# AVRispMK2_V2.net
KiCad netlist of a schematic drawn in EAGLE
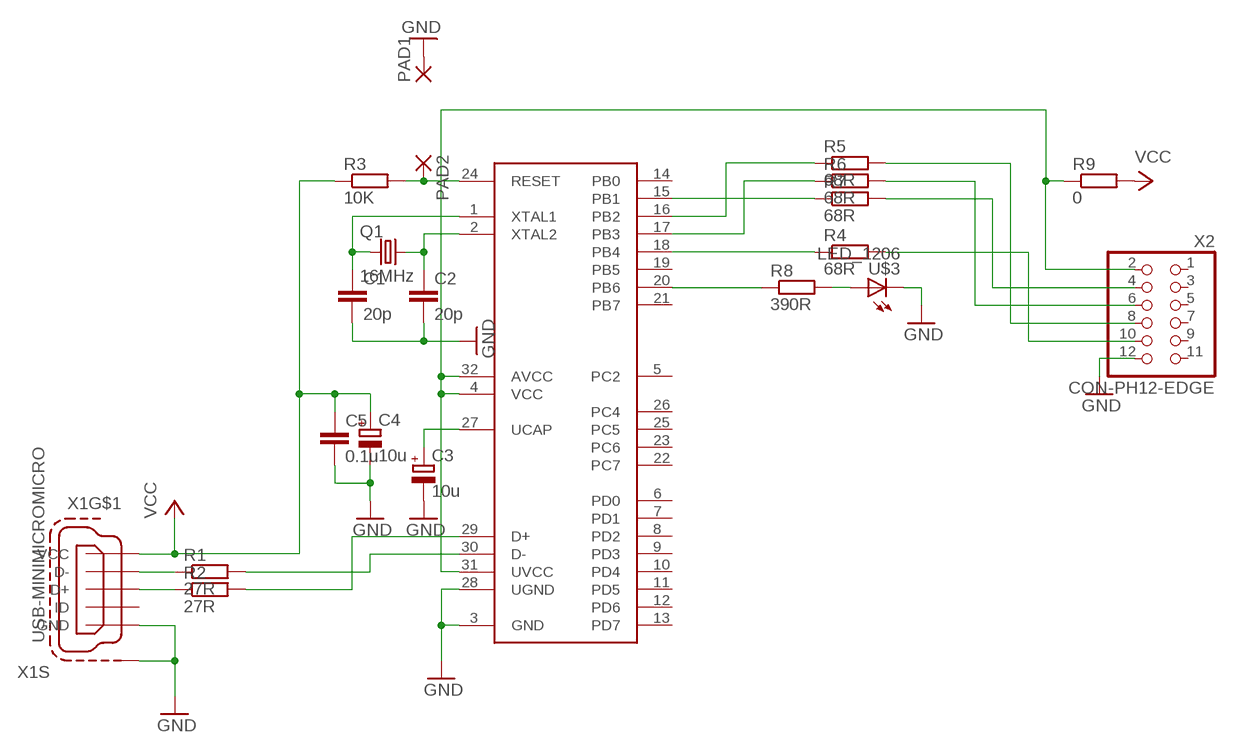
[diagram p0: schematic, sheet 1]

(export (version "E")
  (design (tool "Eeschema 10.0.6"))
  (components
    (comp (ref "C1")
      (value "20p")
      (footprint "eagle-import:C1206")
      (libsource (lib "eagle-import") (part "C-EUC1206"))
    )
    (comp (ref "C2")
      (value "20p")
      (footprint "eagle-import:C1206")
      (libsource (lib "eagle-import") (part "C-EUC1206"))
    )
    (comp (ref "C3")
      (value "10u")
      (footprint "eagle-import:SMC_A")
      (libsource (lib "eagle-import") (part "CPOL-EUSMCA"))
    )
    (comp (ref "C4")
      (value "10u")
      (footprint "eagle-import:SMC_A")
      (libsource (lib "eagle-import") (part "CPOL-EUSMCA"))
    )
    (comp (ref "C5")
      (value "0.1u")
      (footprint "eagle-import:C1206")
      (libsource (lib "eagle-import") (part "C-EUC1206"))
    )
    (comp (ref "PAD1")
      (value "SMD2")
      (footprint "eagle-import:SMD1,27-2,54")
      (libsource (lib "eagle-import") (part "SMD2"))
    )
    (comp (ref "PAD2")
      (value "SMD2")
      (footprint "eagle-import:SMD1,27-2,54")
      (libsource (lib "eagle-import") (part "SMD2"))
    )
    (comp (ref "Q1")
      (value "16MHz")
      (footprint "eagle-import:CRYSTAL-3225")
      (libsource (lib "eagle-import") (part "CRYSTAL3225"))
    )
    (comp (ref "R1")
      (value "27R")
      (footprint "eagle-import:R1206")
      (libsource (lib "eagle-import") (part "R-EU_R1206"))
    )
    (comp (ref "R2")
      (value "27R")
      (footprint "eagle-import:R1206")
      (libsource (lib "eagle-import") (part "R-EU_R1206"))
    )
    (comp (ref "R3")
      (value "10K")
      (footprint "eagle-import:R1206")
      (libsource (lib "eagle-import") (part "R-EU_R1206"))
    )
    (comp (ref "R4")
      (value "68R")
      (footprint "eagle-import:R1206")
      (libsource (lib "eagle-import") (part "R-EU_R1206"))
    )
    (comp (ref "R5")
      (value "68R")
      (footprint "eagle-import:R1206")
      (libsource (lib "eagle-import") (part "R-EU_R1206"))
    )
    (comp (ref "R6")
      (value "68R")
      (footprint "eagle-import:R1206")
      (libsource (lib "eagle-import") (part "R-EU_R1206"))
    )
    (comp (ref "R7")
      (value "68R")
      (footprint "eagle-import:R1206")
      (libsource (lib "eagle-import") (part "R-EU_R1206"))
    )
    (comp (ref "R8")
      (value "390R")
      (footprint "eagle-import:R1206")
      (libsource (lib "eagle-import") (part "R-EU_R1206"))
    )
    (comp (ref "R9")
      (value "0")
      (footprint "eagle-import:R1206")
      (libsource (lib "eagle-import") (part "R-EU_R1206"))
    )
    (comp (ref "U$1")
      (value "AT90USB162")
      (footprint "eagle-import:VQFP32")
      (libsource (lib "eagle-import") (part "AT90USB162"))
    )
    (comp (ref "U$3")
      (value "LED_1206")
      (footprint "eagle-import:LED1206")
      (libsource (lib "eagle-import") (part "LED_1206"))
    )
    (comp (ref "X1")
      (value "USB-MINIMICROMICRO")
      (footprint "eagle-import:USB-B-MICRO-SMD")
      (libsource (lib "eagle-import") (part "USB-MINIMICROMICRO"))
    )
    (comp (ref "X2")
      (value "CON-PH12-EDGE")
      (footprint "eagle-import:ML12_EDGE_SMD")
      (libsource (lib "eagle-import") (part "CON-PH12-EDGE"))
    )
  )
  (nets
    (net (code "1") (name "GND") (class "Default")
      (node (ref "C1") (pin "2") (pinfunction "2_2") (pintype "passive"))
      (node (ref "C2") (pin "2") (pinfunction "2_2") (pintype "passive"))
      (node (ref "C3") (pin "-") (pinfunction "-_-") (pintype "passive"))
      (node (ref "C4") (pin "-") (pinfunction "-_-") (pintype "passive"))
      (node (ref "C5") (pin "2") (pinfunction "2_2") (pintype "passive"))
      (node (ref "PAD1") (pin "1") (pinfunction "P_1") (pintype "passive"))
      (node (ref "U$1") (pin "28") (pinfunction "UGND_28") (pintype "bidirectional"))
      (node (ref "U$1") (pin "3") (pinfunction "GND_3") (pintype "power_in"))
      (node (ref "U$3") (pin "C") (pinfunction "C_C") (pintype "passive"))
      (node (ref "X1") (pin "GND") (pinfunction "GND_GND") (pintype "passive"))
      (node (ref "X1") (pin "SHIELD1") (pinfunction "S1_SHIELD1") (pintype "passive"))
      (node (ref "X1") (pin "SHIELD2") (pinfunction "S1_SHIELD2") (pintype "passive"))
      (node (ref "X1") (pin "SHIELD3") (pinfunction "S1_SHIELD3") (pintype "passive"))
      (node (ref "X2") (pin "12") (pinfunction "12_12") (pintype "passive"))
    )
    (net (code "2") (name "Net-(PAD2-P)") (class "Default")
      (node (ref "PAD2") (pin "1") (pinfunction "P_1") (pintype "passive"))
      (node (ref "R3") (pin "2") (pinfunction "2_2") (pintype "passive"))
      (node (ref "U$1") (pin "24") (pinfunction "RESET_24") (pintype "bidirectional"))
    )
    (net (code "3") (name "Net-(Q1-1)") (class "Default")
      (node (ref "C1") (pin "1") (pinfunction "1_1") (pintype "passive"))
      (node (ref "Q1") (pin "P$2") (pinfunction "1_P$2") (pintype "passive"))
      (node (ref "U$1") (pin "1") (pinfunction "XTAL1_1") (pintype "bidirectional"))
    )
    (net (code "4") (name "Net-(Q1-2)") (class "Default")
      (node (ref "C2") (pin "1") (pinfunction "1_1") (pintype "passive"))
      (node (ref "Q1") (pin "P$4") (pinfunction "2_P$4") (pintype "passive"))
      (node (ref "U$1") (pin "2") (pinfunction "XTAL2_2") (pintype "bidirectional"))
    )
    (net (code "5") (name "Net-(R1-Pad1)") (class "Default")
      (node (ref "R1") (pin "1") (pinfunction "1_1") (pintype "passive"))
      (node (ref "X1") (pin "D-") (pinfunction "D-_D-") (pintype "passive"))
    )
    (net (code "6") (name "Net-(R2-Pad1)") (class "Default")
      (node (ref "R2") (pin "1") (pinfunction "1_1") (pintype "passive"))
      (node (ref "X1") (pin "D+") (pinfunction "D+_D+") (pintype "passive"))
    )
    (net (code "7") (name "Net-(R4-Pad2)") (class "Default")
      (node (ref "R4") (pin "2") (pinfunction "2_2") (pintype "passive"))
      (node (ref "X2") (pin "10") (pinfunction "10_10") (pintype "passive"))
    )
    (net (code "8") (name "Net-(R5-Pad2)") (class "Default")
      (node (ref "R5") (pin "2") (pinfunction "2_2") (pintype "passive"))
      (node (ref "X2") (pin "8") (pinfunction "8_8") (pintype "passive"))
    )
    (net (code "9") (name "Net-(R6-Pad2)") (class "Default")
      (node (ref "R6") (pin "2") (pinfunction "2_2") (pintype "passive"))
      (node (ref "X2") (pin "6") (pinfunction "6_6") (pintype "passive"))
    )
    (net (code "10") (name "Net-(R7-Pad2)") (class "Default")
      (node (ref "R7") (pin "2") (pinfunction "2_2") (pintype "passive"))
      (node (ref "X2") (pin "4") (pinfunction "4_4") (pintype "passive"))
    )
    (net (code "11") (name "Net-(R8-Pad2)") (class "Default")
      (node (ref "R8") (pin "2") (pinfunction "2_2") (pintype "passive"))
      (node (ref "U$3") (pin "A") (pinfunction "A_A") (pintype "passive"))
    )
    (net (code "12") (name "Net-(U$1-AVCC)") (class "Default")
      (node (ref "R9") (pin "1") (pinfunction "1_1") (pintype "passive"))
      (node (ref "U$1") (pin "31") (pinfunction "UVCC_31") (pintype "bidirectional"))
      (node (ref "U$1") (pin "32") (pinfunction "AVCC_32") (pintype "bidirectional"))
      (node (ref "U$1") (pin "4") (pinfunction "VCC_4") (pintype "power_in"))
      (node (ref "X2") (pin "2") (pinfunction "2_2") (pintype "passive"))
    )
    (net (code "13") (name "Net-(U$1-D+)") (class "Default")
      (node (ref "R2") (pin "2") (pinfunction "2_2") (pintype "passive"))
      (node (ref "U$1") (pin "29") (pinfunction "D+_29") (pintype "bidirectional"))
    )
    (net (code "14") (name "Net-(U$1-D-)") (class "Default")
      (node (ref "R1") (pin "2") (pinfunction "2_2") (pintype "passive"))
      (node (ref "U$1") (pin "30") (pinfunction "D-_30") (pintype "bidirectional"))
    )
    (net (code "15") (name "Net-(U$1-PB1)") (class "Default")
      (node (ref "R7") (pin "1") (pinfunction "1_1") (pintype "passive"))
      (node (ref "U$1") (pin "15") (pinfunction "PB1_15") (pintype "bidirectional"))
    )
    (net (code "16") (name "Net-(U$1-PB2)") (class "Default")
      (node (ref "R5") (pin "1") (pinfunction "1_1") (pintype "passive"))
      (node (ref "U$1") (pin "16") (pinfunction "PB2_16") (pintype "bidirectional"))
    )
    (net (code "17") (name "Net-(U$1-PB3)") (class "Default")
      (node (ref "R6") (pin "1") (pinfunction "1_1") (pintype "passive"))
      (node (ref "U$1") (pin "17") (pinfunction "PB3_17") (pintype "bidirectional"))
    )
    (net (code "18") (name "Net-(U$1-PB4)") (class "Default")
      (node (ref "R4") (pin "1") (pinfunction "1_1") (pintype "passive"))
      (node (ref "U$1") (pin "18") (pinfunction "PB4_18") (pintype "bidirectional"))
    )
    (net (code "19") (name "Net-(U$1-PB6)") (class "Default")
      (node (ref "R8") (pin "1") (pinfunction "1_1") (pintype "passive"))
      (node (ref "U$1") (pin "20") (pinfunction "PB6_20") (pintype "bidirectional"))
    )
    (net (code "20") (name "Net-(U$1-UCAP)") (class "Default")
      (node (ref "C3") (pin "+") (pinfunction "+_+") (pintype "passive"))
      (node (ref "U$1") (pin "27") (pinfunction "UCAP_27") (pintype "bidirectional"))
    )
    (net (code "21") (name "VCC") (class "Default")
      (node (ref "C4") (pin "+") (pinfunction "+_+") (pintype "passive"))
      (node (ref "C5") (pin "1") (pinfunction "1_1") (pintype "passive"))
      (node (ref "R3") (pin "1") (pinfunction "1_1") (pintype "passive"))
      (node (ref "R9") (pin "2") (pinfunction "2_2") (pintype "passive"))
      (node (ref "X1") (pin "VBUS") (pinfunction "VCC_VBUS") (pintype "passive"))
    )
    (net (code "22") (name "unconnected-(U$1-PB0-Pad14)") (class "Default")
      (node (ref "U$1") (pin "14") (pinfunction "PB0_14") (pintype "bidirectional"))
    )
    (net (code "23") (name "unconnected-(U$1-PB5-Pad19)") (class "Default")
      (node (ref "U$1") (pin "19") (pinfunction "PB5_19") (pintype "bidirectional"))
    )
    (net (code "24") (name "unconnected-(U$1-PB7-Pad21)") (class "Default")
      (node (ref "U$1") (pin "21") (pinfunction "PB7_21") (pintype "bidirectional"))
    )
    (net (code "25") (name "unconnected-(U$1-PC2-Pad5)") (class "Default")
      (node (ref "U$1") (pin "5") (pinfunction "PC2_5") (pintype "bidirectional"))
    )
    (net (code "26") (name "unconnected-(U$1-PC4-Pad26)") (class "Default")
      (node (ref "U$1") (pin "26") (pinfunction "PC4_26") (pintype "bidirectional"))
    )
    (net (code "27") (name "unconnected-(U$1-PC5-Pad25)") (class "Default")
      (node (ref "U$1") (pin "25") (pinfunction "PC5_25") (pintype "bidirectional"))
    )
    (net (code "28") (name "unconnected-(U$1-PC6-Pad23)") (class "Default")
      (node (ref "U$1") (pin "23") (pinfunction "PC6_23") (pintype "bidirectional"))
    )
    (net (code "29") (name "unconnected-(U$1-PC7-Pad22)") (class "Default")
      (node (ref "U$1") (pin "22") (pinfunction "PC7_22") (pintype "bidirectional"))
    )
    (net (code "30") (name "unconnected-(U$1-PD0-Pad6)") (class "Default")
      (node (ref "U$1") (pin "6") (pinfunction "PD0_6") (pintype "bidirectional"))
    )
    (net (code "31") (name "unconnected-(U$1-PD1-Pad7)") (class "Default")
      (node (ref "U$1") (pin "7") (pinfunction "PD1_7") (pintype "bidirectional"))
    )
    (net (code "32") (name "unconnected-(U$1-PD2-Pad8)") (class "Default")
      (node (ref "U$1") (pin "8") (pinfunction "PD2_8") (pintype "bidirectional"))
    )
    (net (code "33") (name "unconnected-(U$1-PD3-Pad9)") (class "Default")
      (node (ref "U$1") (pin "9") (pinfunction "PD3_9") (pintype "bidirectional"))
    )
    (net (code "34") (name "unconnected-(U$1-PD4-Pad10)") (class "Default")
      (node (ref "U$1") (pin "10") (pinfunction "PD4_10") (pintype "bidirectional"))
    )
    (net (code "35") (name "unconnected-(U$1-PD5-Pad11)") (class "Default")
      (node (ref "U$1") (pin "11") (pinfunction "PD5_11") (pintype "bidirectional"))
    )
    (net (code "36") (name "unconnected-(U$1-PD6-Pad12)") (class "Default")
      (node (ref "U$1") (pin "12") (pinfunction "PD6_12") (pintype "bidirectional"))
    )
    (net (code "37") (name "unconnected-(U$1-PD7-Pad13)") (class "Default")
      (node (ref "U$1") (pin "13") (pinfunction "PD7_13") (pintype "bidirectional"))
    )
    (net (code "38") (name "unconnected-(X1-PadID)") (class "Default")
      (node (ref "X1") (pin "ID") (pinfunction "ID_ID") (pintype "passive"))
    )
    (net (code "39") (name "unconnected-(X2-Pad1)") (class "Default")
      (node (ref "X2") (pin "1") (pinfunction "1_1") (pintype "passive"))
    )
    (net (code "40") (name "unconnected-(X2-Pad3)") (class "Default")
      (node (ref "X2") (pin "3") (pinfunction "3_3") (pintype "passive"))
    )
    (net (code "41") (name "unconnected-(X2-Pad5)") (class "Default")
      (node (ref "X2") (pin "5") (pinfunction "5_5") (pintype "passive"))
    )
    (net (code "42") (name "unconnected-(X2-Pad7)") (class "Default")
      (node (ref "X2") (pin "7") (pinfunction "7_7") (pintype "passive"))
    )
    (net (code "43") (name "unconnected-(X2-Pad9)") (class "Default")
      (node (ref "X2") (pin "9") (pinfunction "9_9") (pintype "passive"))
    )
    (net (code "44") (name "unconnected-(X2-Pad11)") (class "Default")
      (node (ref "X2") (pin "11") (pinfunction "11_11") (pintype "passive"))
    )
  )
)
